# AC6901Demo0.net
KiCad netlist of a schematic drawn in Altium Designer
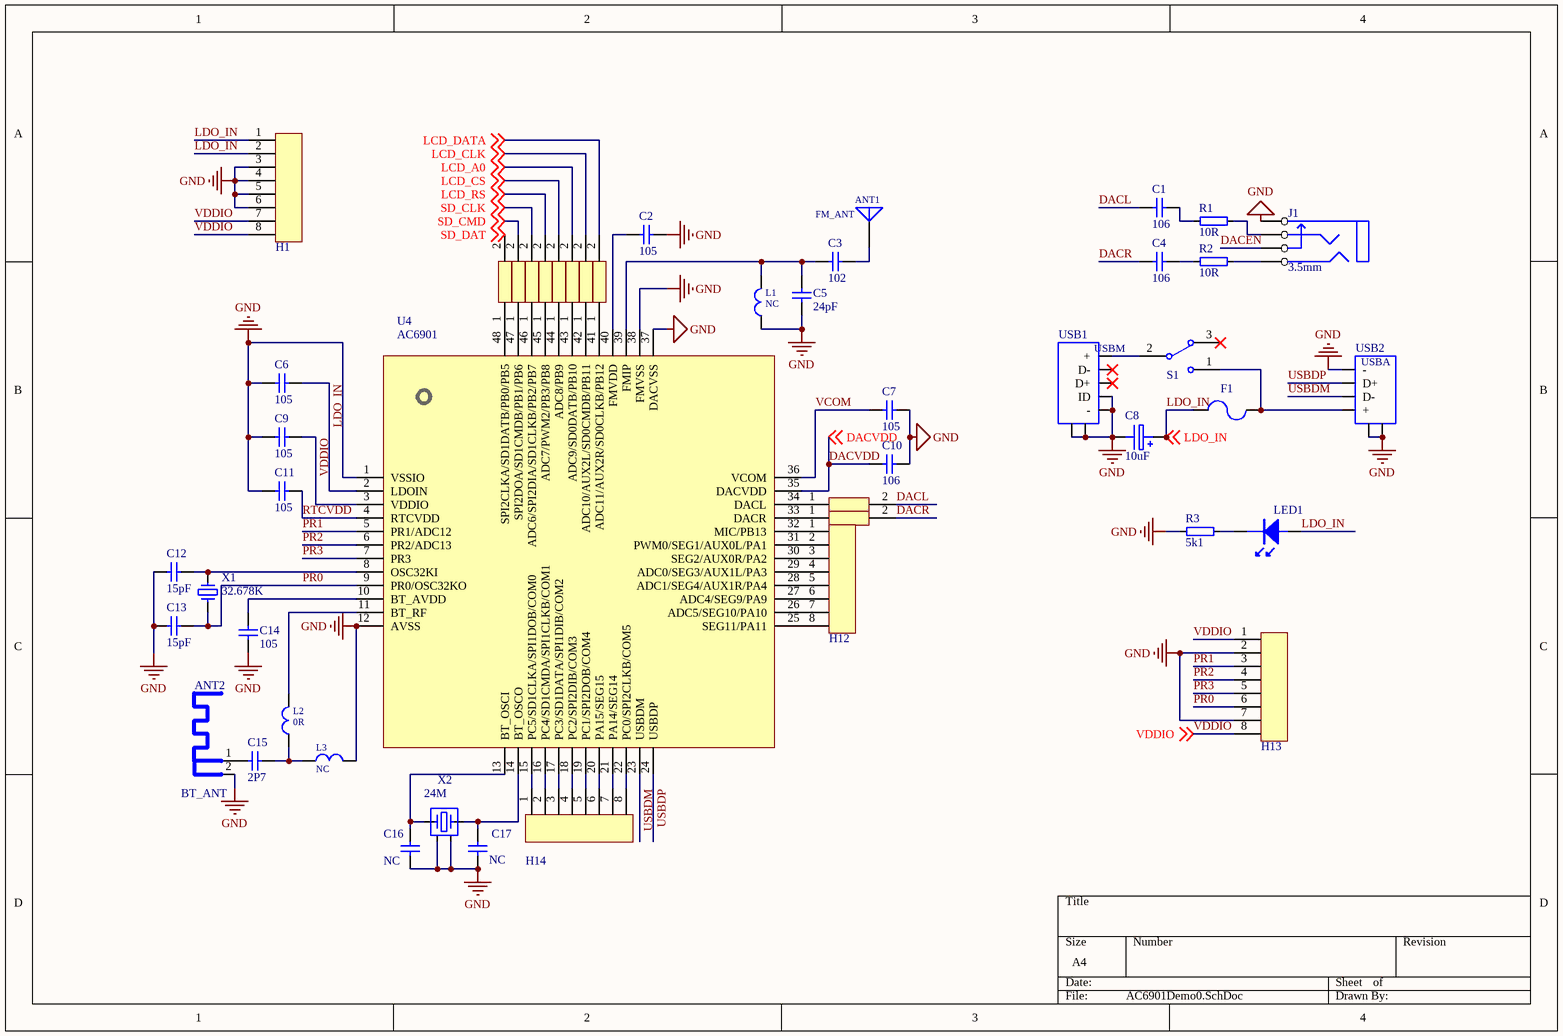
[diagram p0: AC6901Demo0.SchDoc]

(export (version "E")
  (design (tool "Eeschema 10.0.6"))
  (components
    (comp (ref "ANT1") (value "FM_ANT") (footprint "Demo:FM_ANT") (libsource (lib "Demo") (part "FM_ANT")))
    (comp (ref "ANT2")
      (value "BT_ANT")
      (footprint "Demo:ANT-F-2-2.4G")
      (libsource (lib "Demo") (part "BT_ANT"))
    )
    (comp (ref "C1") (value "106") (footprint "Demo:C 0805") (libsource (lib "Demo") (part "CAP-MLCC")))
    (comp (ref "C2") (value "105") (footprint "Demo:C 0805") (libsource (lib "Demo") (part "CAP-MLCC")))
    (comp (ref "C3") (value "102") (footprint "Demo:C 0805") (libsource (lib "Demo") (part "CAP-MLCC")))
    (comp (ref "C4") (value "106") (footprint "Demo:C 0805") (libsource (lib "Demo") (part "CAP-MLCC")))
    (comp (ref "C5") (value "24pF") (footprint "Demo:C 0805") (libsource (lib "Demo") (part "CAP-MLCC")))
    (comp (ref "C6") (value "105") (footprint "Demo:C 0805") (libsource (lib "Demo") (part "CAP-MLCC")))
    (comp (ref "C7") (value "105") (footprint "Demo:C 0805") (libsource (lib "Demo") (part "CAP-MLCC")))
    (comp (ref "C8") (value "10uF") (footprint "Demo:CTan(6032)") (libsource (lib "Demo") (part "CAP-ALE")))
    (comp (ref "C9") (value "105") (footprint "Demo:C 0805") (libsource (lib "Demo") (part "CAP-MLCC")))
    (comp (ref "C10") (value "106") (footprint "Demo:C 0805") (libsource (lib "Demo") (part "CAP-MLCC")))
    (comp (ref "C11") (value "105") (footprint "Demo:C 0805") (libsource (lib "Demo") (part "CAP-MLCC")))
    (comp (ref "C12") (value "15pF") (footprint "Demo:C 0805") (libsource (lib "Demo") (part "CAP-MLCC")))
    (comp (ref "C13") (value "15pF") (footprint "Demo:C 0805") (libsource (lib "Demo") (part "CAP-MLCC")))
    (comp (ref "C14") (value "105") (footprint "Demo:C 0805") (libsource (lib "Demo") (part "CAP-MLCC")))
    (comp (ref "C15") (value "2P7") (footprint "Demo:C 0805") (libsource (lib "Demo") (part "CAP-MLCC")))
    (comp (ref "C16") (value "NC") (footprint "Demo:C 0805") (libsource (lib "Demo") (part "CAP-MLCC")))
    (comp (ref "C17") (value "NC") (footprint "Demo:C 0805") (libsource (lib "Demo") (part "CAP-MLCC")))
    (comp (ref "F1") (value "FUSE") (footprint "Demo:F1808") (libsource (lib "Demo") (part "FUSE")))
    (comp (ref "H1") (value "HDR1X8") (footprint "Demo:HDR1X8") (libsource (lib "Demo") (part "HDR1X8")))
    (comp (ref "H2") (value "HDR2X1") (footprint "Demo:HDR2X1") (libsource (lib "") (part "HDR2X1_1")))
    (comp (ref "H3") (value "HDR2X1") (footprint "Demo:HDR2X1") (libsource (lib "") (part "HDR2X1_1")))
    (comp (ref "H4") (value "HDR2X1") (footprint "Demo:HDR2X1") (libsource (lib "") (part "HDR2X1_1")))
    (comp (ref "H5") (value "HDR2X1") (footprint "Demo:HDR2X1") (libsource (lib "") (part "HDR2X1_1")))
    (comp (ref "H6") (value "HDR2X1") (footprint "Demo:HDR2X1") (libsource (lib "") (part "HDR2X1_1")))
    (comp (ref "H7") (value "HDR2X1") (footprint "Demo:HDR2X1") (libsource (lib "") (part "HDR2X1_1")))
    (comp (ref "H8") (value "HDR2X1") (footprint "Demo:HDR2X1") (libsource (lib "") (part "HDR2X1_1")))
    (comp (ref "H9") (value "HDR2X1") (footprint "Demo:HDR2X1") (libsource (lib "") (part "HDR2X1_1")))
    (comp (ref "H10") (value "HDR2X1") (footprint "Demo:HDR2X1") (libsource (lib "Demo") (part "HDR2X1")))
    (comp (ref "H11") (value "HDR2X1") (footprint "Demo:HDR2X1") (libsource (lib "Demo") (part "HDR2X1")))
    (comp (ref "H12") (value "HDR1X8") (footprint "Demo:HDR1X8") (libsource (lib "Demo") (part "HDR1X8")))
    (comp (ref "H13") (value "HDR1X8") (footprint "Demo:HDR1X8") (libsource (lib "Demo") (part "HDR1X8")))
    (comp (ref "H14") (value "HDR1X8") (footprint "Demo:HDR1X8") (libsource (lib "") (part "HDR1X8_1")))
    (comp (ref "J1") (value "3.5mm") (footprint "Demo:AUX-3.5") (libsource (lib "Demo") (part "立体声插头")))
    (comp (ref "L1") (value "NC") (footprint "Demo:L 0805") (libsource (lib "Demo") (part "INDUCTOR")))
    (comp (ref "L2") (value "0R") (footprint "Demo:L 0805") (libsource (lib "Demo") (part "INDUCTOR")))
    (comp (ref "L3") (value "NC") (footprint "Demo:L 0805") (libsource (lib "Demo") (part "INDUCTOR")))
    (comp (ref "LED1") (value "LED") (footprint "Demo:LED 0805B") (libsource (lib "Demo") (part "LED")))
    (comp (ref "R1") (value "10R") (footprint "Demo:R 0805") (libsource (lib "Demo") (part "RES")))
    (comp (ref "R2") (value "10R") (footprint "Demo:R 0805") (libsource (lib "Demo") (part "RES")))
    (comp (ref "R3") (value "5k1") (footprint "Demo:R 0805") (libsource (lib "Demo") (part "RES")))
    (comp (ref "S1")
      (value "SW-SPDT")
      (footprint "Demo:MSK-12C01-07")
      (fields (field (name "PUBLISHER") "Altium Limited"))
      (libsource (lib "Demo") (part "SW-SPDT"))
    )
    (comp (ref "U4") (value "AC6901") (footprint "Demo:LQPF48") (libsource (lib "Demo") (part "AC6901")))
    (comp (ref "USB1")
      (value "USBmirco")
      (footprint "Demo:USB_micro")
      (libsource (lib "Demo") (part "USBmirco"))
    )
    (comp (ref "USB2") (value "USBA") (footprint "Demo:USB-A") (libsource (lib "Demo") (part "USBA")))
    (comp (ref "X1") (value "32.678K") (footprint "Demo:XTAL_3X8") (libsource (lib "Demo") (part "XTAL_3X8")))
    (comp (ref "X2")
      (value "24M")
      (footprint "Demo:XTAL_3225-4P")
      (libsource (lib "Demo") (part "XTAL_3325-4"))
    )
  )
  (nets
    (net (code "1") (name "/DACEN") (class "Default")
      (node (ref "J1") (pin "4") (pinfunction "4_4") (pintype "passive"))
    )
    (net (code "2") (name "/DACL") (class "Default")
      (node (ref "C1") (pin "1") (pinfunction "1_1") (pintype "passive"))
      (node (ref "H10") (pin "2") (pinfunction "2_2") (pintype "passive"))
    )
    (net (code "3") (name "/DACR") (class "Default")
      (node (ref "C4") (pin "1") (pinfunction "1_1") (pintype "passive"))
      (node (ref "H11") (pin "2") (pinfunction "2_2") (pintype "passive"))
    )
    (net (code "4") (name "/PR0") (class "Default")
      (node (ref "C13") (pin "2") (pinfunction "2_2") (pintype "passive"))
      (node (ref "H13") (pin "6") (pinfunction "6_6") (pintype "passive"))
      (node (ref "U4") (pin "9") (pinfunction "PR0/OSC32KO_9") (pintype "passive"))
      (node (ref "X1") (pin "2") (pinfunction "2_2") (pintype "passive"))
    )
    (net (code "5") (name "/PR1") (class "Default")
      (node (ref "H13") (pin "3") (pinfunction "3_3") (pintype "passive"))
      (node (ref "U4") (pin "5") (pinfunction "PR1/ADC12_5") (pintype "passive"))
    )
    (net (code "6") (name "/PR2") (class "Default")
      (node (ref "H13") (pin "4") (pinfunction "4_4") (pintype "passive"))
      (node (ref "U4") (pin "6") (pinfunction "PR2/ADC13_6") (pintype "passive"))
    )
    (net (code "7") (name "/PR3") (class "Default")
      (node (ref "H13") (pin "5") (pinfunction "5_5") (pintype "passive"))
      (node (ref "U4") (pin "7") (pinfunction "PR3_7") (pintype "passive"))
    )
    (net (code "8") (name "/RTCVDD") (class "Default")
      (node (ref "C11") (pin "1") (pinfunction "1_1") (pintype "passive"))
      (node (ref "U4") (pin "4") (pinfunction "RTCVDD_4") (pintype "passive"))
    )
    (net (code "9") (name "/USBDM") (class "Default")
      (node (ref "U4") (pin "23") (pinfunction "USBDM_23") (pintype "passive"))
      (node (ref "USB2") (pin "2") (pinfunction "D-_2") (pintype "passive"))
    )
    (net (code "10") (name "/USBDP") (class "Default")
      (node (ref "U4") (pin "24") (pinfunction "USBDP_24") (pintype "passive"))
      (node (ref "USB2") (pin "3") (pinfunction "D+_3") (pintype "passive"))
    )
    (net (code "11") (name "/VCOM") (class "Default")
      (node (ref "C7") (pin "1") (pinfunction "1_1") (pintype "passive"))
      (node (ref "U4") (pin "36") (pinfunction "VCOM_36") (pintype "passive"))
    )
    (net (code "12") (name "DACVDD") (class "Default")
      (node (ref "C10") (pin "1") (pinfunction "1_1") (pintype "passive"))
      (node (ref "U4") (pin "35") (pinfunction "DACVDD_35") (pintype "passive"))
    )
    (net (code "13") (name "GND") (class "Default")
      (node (ref "ANT2") (pin "2") (pinfunction "2_2") (pintype "passive"))
      (node (ref "C10") (pin "2") (pinfunction "2_2") (pintype "passive"))
      (node (ref "C11") (pin "2") (pinfunction "2_2") (pintype "passive"))
      (node (ref "C12") (pin "1") (pinfunction "1_1") (pintype "passive"))
      (node (ref "C13") (pin "1") (pinfunction "1_1") (pintype "passive"))
      (node (ref "C14") (pin "1") (pinfunction "1_1") (pintype "passive"))
      (node (ref "C16") (pin "2") (pinfunction "2_2") (pintype "passive"))
      (node (ref "C17") (pin "1") (pinfunction "1_1") (pintype "passive"))
      (node (ref "C2") (pin "1") (pinfunction "1_1") (pintype "passive"))
      (node (ref "C5") (pin "2") (pinfunction "2_2") (pintype "passive"))
      (node (ref "C6") (pin "2") (pinfunction "2_2") (pintype "passive"))
      (node (ref "C7") (pin "2") (pinfunction "2_2") (pintype "passive"))
      (node (ref "C8") (pin "2") (pinfunction "2_2") (pintype "passive"))
      (node (ref "C9") (pin "2") (pinfunction "2_2") (pintype "passive"))
      (node (ref "H1") (pin "3") (pinfunction "3_3") (pintype "passive"))
      (node (ref "H1") (pin "4") (pinfunction "4_4") (pintype "passive"))
      (node (ref "H1") (pin "5") (pinfunction "5_5") (pintype "passive"))
      (node (ref "H1") (pin "6") (pinfunction "6_6") (pintype "passive"))
      (node (ref "H13") (pin "2") (pinfunction "2_2") (pintype "passive"))
      (node (ref "H13") (pin "7") (pinfunction "7_7") (pintype "passive"))
      (node (ref "J1") (pin "1") (pinfunction "1_1") (pintype "passive"))
      (node (ref "L1") (pin "1") (pinfunction "1_1") (pintype "passive"))
      (node (ref "L3") (pin "2") (pinfunction "2_2") (pintype "passive"))
      (node (ref "R3") (pin "1") (pinfunction "1_1") (pintype "passive"))
      (node (ref "U4") (pin "1") (pinfunction "VSSIO_1") (pintype "power_in"))
      (node (ref "U4") (pin "12") (pinfunction "AVSS_12") (pintype "passive"))
      (node (ref "U4") (pin "37") (pinfunction "DACVSS_37") (pintype "passive"))
      (node (ref "U4") (pin "38") (pinfunction "FMVSS_38") (pintype "passive"))
      (node (ref "USB1") (pin "4") (pinfunction "ID_4") (pintype "passive"))
      (node (ref "USB1") (pin "5") (pinfunction "-_5") (pintype "passive"))
      (node (ref "USB1") (pin "GND") (pinfunction "GND_GND") (pintype "passive"))
      (node (ref "USB2") (pin "4") (pinfunction "-_4") (pintype "passive"))
      (node (ref "USB2") (pin "5") (pinfunction "GND_5") (pintype "passive"))
      (node (ref "X2") (pin "2") (pinfunction "2_2") (pintype "passive"))
      (node (ref "X2") (pin "4") (pinfunction "4_4") (pintype "passive"))
    )
    (net (code "14") (name "LCD_A0") (class "Default")
      (node (ref "H7") (pin "2") (pinfunction "2_2") (pintype "passive"))
    )
    (net (code "15") (name "LCD_CLK") (class "Default")
      (node (ref "H8") (pin "2") (pinfunction "2_2") (pintype "passive"))
    )
    (net (code "16") (name "LCD_CS") (class "Default")
      (node (ref "H6") (pin "2") (pinfunction "2_2") (pintype "passive"))
    )
    (net (code "17") (name "LCD_DATA") (class "Default")
      (node (ref "H9") (pin "2") (pinfunction "2_2") (pintype "passive"))
    )
    (net (code "18") (name "LCD_RS") (class "Default")
      (node (ref "H5") (pin "2") (pinfunction "2_2") (pintype "passive"))
    )
    (net (code "19") (name "LDO_IN") (class "Default")
      (node (ref "C6") (pin "1") (pinfunction "1_1") (pintype "passive"))
      (node (ref "C8") (pin "1") (pinfunction "1_1") (pintype "passive"))
      (node (ref "F1") (pin "1") (pinfunction "1_1") (pintype "passive"))
      (node (ref "H1") (pin "1") (pinfunction "1_1") (pintype "passive"))
      (node (ref "H1") (pin "2") (pinfunction "2_2") (pintype "passive"))
      (node (ref "LED1") (pin "1") (pinfunction "1_1") (pintype "passive"))
      (node (ref "U4") (pin "2") (pinfunction "LDOIN_2") (pintype "power_in"))
    )
    (net (code "20") (name "Net-(ANT1-Pad1)") (class "Default")
      (node (ref "ANT1") (pin "1") (pinfunction "1_1") (pintype "passive"))
      (node (ref "C3") (pin "2") (pinfunction "2_2") (pintype "passive"))
    )
    (net (code "21") (name "Net-(ANT2-Pad1)") (class "Default")
      (node (ref "ANT2") (pin "1") (pinfunction "1_1") (pintype "passive"))
      (node (ref "C15") (pin "1") (pinfunction "1_1") (pintype "passive"))
    )
    (net (code "22") (name "Net-(C1-Pad2)") (class "Default")
      (node (ref "C1") (pin "2") (pinfunction "2_2") (pintype "passive"))
      (node (ref "R1") (pin "1") (pinfunction "1_1") (pintype "passive"))
    )
    (net (code "23") (name "Net-(C4-Pad2)") (class "Default")
      (node (ref "C4") (pin "2") (pinfunction "2_2") (pintype "passive"))
      (node (ref "R2") (pin "1") (pinfunction "1_1") (pintype "passive"))
    )
    (net (code "24") (name "Net-(C15-Pad2)") (class "Default")
      (node (ref "C15") (pin "2") (pinfunction "2_2") (pintype "passive"))
      (node (ref "L2") (pin "1") (pinfunction "1_1") (pintype "passive"))
      (node (ref "L3") (pin "1") (pinfunction "1_1") (pintype "passive"))
    )
    (net (code "25") (name "Net-(J1-Pad2)") (class "Default")
      (node (ref "J1") (pin "2") (pinfunction "2_2") (pintype "passive"))
      (node (ref "R1") (pin "2") (pinfunction "2_2") (pintype "passive"))
    )
    (net (code "26") (name "Net-(J1-Pad3)") (class "Default")
      (node (ref "J1") (pin "3") (pinfunction "3_3") (pintype "passive"))
      (node (ref "R2") (pin "2") (pinfunction "2_2") (pintype "passive"))
    )
    (net (code "27") (name "Net-(LED1-Pad2)") (class "Default")
      (node (ref "LED1") (pin "2") (pinfunction "2_2") (pintype "passive"))
      (node (ref "R3") (pin "2") (pinfunction "2_2") (pintype "passive"))
    )
    (net (code "28") (name "Net-(U4-ADC0{slash}SEG3{slash}AUX1L{slash}PA3)") (class "Default")
      (node (ref "H12") (pin "4") (pinfunction "4_4") (pintype "passive"))
      (node (ref "U4") (pin "29") (pinfunction "ADC0/SEG3/AUX1L/PA3_29") (pintype "passive"))
    )
    (net (code "29") (name "Net-(U4-ADC1{slash}SEG4{slash}AUX1R{slash}PA4)") (class "Default")
      (node (ref "H12") (pin "5") (pinfunction "5_5") (pintype "passive"))
      (node (ref "U4") (pin "28") (pinfunction "ADC1/SEG4/AUX1R/PA4_28") (pintype "passive"))
    )
    (net (code "30") (name "Net-(U4-ADC4{slash}SEG9{slash}PA9)") (class "Default")
      (node (ref "H12") (pin "6") (pinfunction "6_6") (pintype "passive"))
      (node (ref "U4") (pin "27") (pinfunction "ADC4/SEG9/PA9_27") (pintype "passive"))
    )
    (net (code "31") (name "Net-(U4-ADC5{slash}SEG10{slash}PA10)") (class "Default")
      (node (ref "H12") (pin "7") (pinfunction "7_7") (pintype "passive"))
      (node (ref "U4") (pin "26") (pinfunction "ADC5/SEG10/PA10_26") (pintype "passive"))
    )
    (net (code "32") (name "Net-(U4-ADC6{slash}SPI2DIA{slash}SD1CLKB{slash}PB2{slash}PB7)") (class "Default")
      (node (ref "H4") (pin "1") (pinfunction "1_1") (pintype "passive"))
      (node (ref "U4") (pin "46") (pinfunction "ADC6/SPI2DIA/SD1CLKB/PB2/PB7_46") (pintype "passive"))
    )
    (net (code "33") (name "Net-(U4-ADC7{slash}PWM2{slash}PB3{slash}PB8)") (class "Default")
      (node (ref "H5") (pin "1") (pinfunction "1_1") (pintype "passive"))
      (node (ref "U4") (pin "45") (pinfunction "ADC7/PWM2/PB3/PB8_45") (pintype "passive"))
    )
    (net (code "34") (name "Net-(U4-ADC8{slash}PB9)") (class "Default")
      (node (ref "H6") (pin "1") (pinfunction "1_1") (pintype "passive"))
      (node (ref "U4") (pin "44") (pinfunction "ADC8/PB9_44") (pintype "passive"))
    )
    (net (code "35") (name "Net-(U4-ADC9{slash}SD0DATB{slash}PB10)") (class "Default")
      (node (ref "H7") (pin "1") (pinfunction "1_1") (pintype "passive"))
      (node (ref "U4") (pin "43") (pinfunction "ADC9/SD0DATB/PB10_43") (pintype "passive"))
    )
    (net (code "36") (name "Net-(U4-ADC10{slash}AUX2L{slash}SD0CMDB{slash}PB11)") (class "Default")
      (node (ref "H8") (pin "1") (pinfunction "1_1") (pintype "passive"))
      (node (ref "U4") (pin "42") (pinfunction "ADC10/AUX2L/SD0CMDB/PB11_42") (pintype "passive"))
    )
    (net (code "37") (name "Net-(U4-ADC11{slash}AUX2R{slash}SD0CLKB{slash}PB12)") (class "Default")
      (node (ref "H9") (pin "1") (pinfunction "1_1") (pintype "passive"))
      (node (ref "U4") (pin "41") (pinfunction "ADC11/AUX2R/SD0CLKB/PB12_41") (pintype "passive"))
    )
    (net (code "38") (name "Net-(U4-BT_AVDD)") (class "Default")
      (node (ref "C14") (pin "2") (pinfunction "2_2") (pintype "passive"))
      (node (ref "U4") (pin "10") (pinfunction "BT_AVDD_10") (pintype "passive"))
    )
    (net (code "39") (name "Net-(U4-BT_OSCI)") (class "Default")
      (node (ref "C16") (pin "1") (pinfunction "1_1") (pintype "passive"))
      (node (ref "U4") (pin "13") (pinfunction "BT_OSCI_13") (pintype "passive"))
      (node (ref "X2") (pin "3") (pinfunction "3_3") (pintype "passive"))
    )
    (net (code "40") (name "Net-(U4-BT_OSCO)") (class "Default")
      (node (ref "C17") (pin "2") (pinfunction "2_2") (pintype "passive"))
      (node (ref "U4") (pin "14") (pinfunction "BT_OSCO_14") (pintype "passive"))
      (node (ref "X2") (pin "1") (pinfunction "1_1") (pintype "passive"))
    )
    (net (code "41") (name "Net-(U4-BT_RF)") (class "Default")
      (node (ref "L2") (pin "2") (pinfunction "2_2") (pintype "passive"))
      (node (ref "U4") (pin "11") (pinfunction "BT_RF_11") (pintype "passive"))
    )
    (net (code "42") (name "Net-(U4-DACL)") (class "Default")
      (node (ref "H10") (pin "1") (pinfunction "1_1") (pintype "passive"))
      (node (ref "U4") (pin "34") (pinfunction "DACL_34") (pintype "passive"))
    )
    (net (code "43") (name "Net-(U4-DACR)") (class "Default")
      (node (ref "H11") (pin "1") (pinfunction "1_1") (pintype "passive"))
      (node (ref "U4") (pin "33") (pinfunction "DACR_33") (pintype "passive"))
    )
    (net (code "44") (name "Net-(U4-FMIP)") (class "Default")
      (node (ref "C3") (pin "1") (pinfunction "1_1") (pintype "passive"))
      (node (ref "C5") (pin "1") (pinfunction "1_1") (pintype "passive"))
      (node (ref "L1") (pin "2") (pinfunction "2_2") (pintype "passive"))
      (node (ref "U4") (pin "39") (pinfunction "FMIP_39") (pintype "passive"))
    )
    (net (code "45") (name "Net-(U4-FMVDD)") (class "Default")
      (node (ref "C2") (pin "2") (pinfunction "2_2") (pintype "passive"))
      (node (ref "U4") (pin "40") (pinfunction "FMVDD_40") (pintype "passive"))
    )
    (net (code "46") (name "Net-(U4-MIC{slash}PB13)") (class "Default")
      (node (ref "H12") (pin "1") (pinfunction "1_1") (pintype "passive"))
      (node (ref "U4") (pin "32") (pinfunction "MIC/PB13_32") (pintype "passive"))
    )
    (net (code "47") (name "Net-(U4-OSC32KI)") (class "Default")
      (node (ref "C12") (pin "2") (pinfunction "2_2") (pintype "passive"))
      (node (ref "U4") (pin "8") (pinfunction "OSC32KI_8") (pintype "passive"))
      (node (ref "X1") (pin "1") (pinfunction "1_1") (pintype "passive"))
    )
    (net (code "48") (name "Net-(U4-PA14{slash}SEG14)") (class "Default")
      (node (ref "H14") (pin "7") (pinfunction "7_7") (pintype "passive"))
      (node (ref "U4") (pin "21") (pinfunction "PA14/SEG14_21") (pintype "passive"))
    )
    (net (code "49") (name "Net-(U4-PA15{slash}SEG15)") (class "Default")
      (node (ref "H14") (pin "6") (pinfunction "6_6") (pintype "passive"))
      (node (ref "U4") (pin "20") (pinfunction "PA15/SEG15_20") (pintype "passive"))
    )
    (net (code "50") (name "Net-(U4-PC0{slash}SPI2CLKB{slash}COM5)") (class "Default")
      (node (ref "H14") (pin "8") (pinfunction "8_8") (pintype "passive"))
      (node (ref "U4") (pin "22") (pinfunction "PC0/SPI2CLKB/COM5_22") (pintype "passive"))
    )
    (net (code "51") (name "Net-(U4-PC1{slash}SPI2DOB{slash}COM4)") (class "Default")
      (node (ref "H14") (pin "5") (pinfunction "5_5") (pintype "passive"))
      (node (ref "U4") (pin "19") (pinfunction "PC1/SPI2DOB/COM4_19") (pintype "passive"))
    )
    (net (code "52") (name "Net-(U4-PC2{slash}SPI2DIB{slash}COM3)") (class "Default")
      (node (ref "H14") (pin "4") (pinfunction "4_4") (pintype "passive"))
      (node (ref "U4") (pin "18") (pinfunction "PC2/SPI2DIB/COM3_18") (pintype "passive"))
    )
    (net (code "53") (name "Net-(U4-PC3{slash}SD1DATA{slash}SPI1DIB{slash}COM2)") (class "Default")
      (node (ref "H14") (pin "3") (pinfunction "3_3") (pintype "passive"))
      (node (ref "U4") (pin "17") (pinfunction "PC3/SD1DATA/SPI1DIB/COM2_17") (pintype "passive"))
    )
    (net (code "54") (name "Net-(U4-PC4{slash}SD1CMDA{slash}SPI1CLKB{slash}COM1)") (class "Default")
      (node (ref "H14") (pin "2") (pinfunction "2_2") (pintype "passive"))
      (node (ref "U4") (pin "16") (pinfunction "PC4/SD1CMDA/SPI1CLKB/COM1_16") (pintype "passive"))
    )
    (net (code "55") (name "Net-(U4-PC5{slash}SD1CLKA{slash}SPI1DOB{slash}COM0)") (class "Default")
      (node (ref "H14") (pin "1") (pinfunction "1_1") (pintype "passive"))
      (node (ref "U4") (pin "15") (pinfunction "PC5/SD1CLKA/SPI1DOB/COM0_15") (pintype "passive"))
    )
    (net (code "56") (name "Net-(U4-PWM0{slash}SEG1{slash}AUX0L{slash}PA1)") (class "Default")
      (node (ref "H12") (pin "2") (pinfunction "2_2") (pintype "passive"))
      (node (ref "U4") (pin "31") (pinfunction "PWM0/SEG1/AUX0L/PA1_31") (pintype "passive"))
    )
    (net (code "57") (name "Net-(U4-SEG2{slash}AUX0R{slash}PA2)") (class "Default")
      (node (ref "H12") (pin "3") (pinfunction "3_3") (pintype "passive"))
      (node (ref "U4") (pin "30") (pinfunction "SEG2/AUX0R/PA2_30") (pintype "passive"))
    )
    (net (code "58") (name "Net-(U4-SEG11{slash}PA11)") (class "Default")
      (node (ref "H12") (pin "8") (pinfunction "8_8") (pintype "passive"))
      (node (ref "U4") (pin "25") (pinfunction "SEG11/PA11_25") (pintype "passive"))
    )
    (net (code "59") (name "Net-(U4-SPI2CLKA{slash}SD1DATB{slash}PB0{slash}PB5)") (class "Default")
      (node (ref "H2") (pin "1") (pinfunction "1_1") (pintype "passive"))
      (node (ref "U4") (pin "48") (pinfunction "SPI2CLKA/SD1DATB/PB0/PB5_48") (pintype "passive"))
    )
    (net (code "60") (name "Net-(U4-SPI2DOA{slash}SD1CMDB{slash}PB1{slash}PB6)") (class "Default")
      (node (ref "H3") (pin "1") (pinfunction "1_1") (pintype "passive"))
      (node (ref "U4") (pin "47") (pinfunction "SPI2DOA/SD1CMDB/PB1/PB6_47") (pintype "passive"))
    )
    (net (code "61") (name "Net-(USB1-+)") (class "Default")
      (node (ref "S1") (pin "2") (pinfunction "2_2") (pintype "passive"))
      (node (ref "USB1") (pin "1") (pinfunction "+_1") (pintype "passive"))
    )
    (net (code "62") (name "Net-(USB2-+)") (class "Default")
      (node (ref "F1") (pin "2") (pinfunction "2_2") (pintype "passive"))
      (node (ref "S1") (pin "1") (pinfunction "1_1") (pintype "passive"))
      (node (ref "USB2") (pin "1") (pinfunction "+_1") (pintype "passive"))
    )
    (net (code "63") (name "SD_CLK") (class "Default")
      (node (ref "H4") (pin "2") (pinfunction "2_2") (pintype "passive"))
    )
    (net (code "64") (name "SD_CMD") (class "Default")
      (node (ref "H3") (pin "2") (pinfunction "2_2") (pintype "passive"))
    )
    (net (code "65") (name "SD_DAT") (class "Default")
      (node (ref "H2") (pin "2") (pinfunction "2_2") (pintype "passive"))
    )
    (net (code "66") (name "VDDIO") (class "Default")
      (node (ref "C9") (pin "1") (pinfunction "1_1") (pintype "passive"))
      (node (ref "H1") (pin "7") (pinfunction "7_7") (pintype "passive"))
      (node (ref "H1") (pin "8") (pinfunction "8_8") (pintype "passive"))
      (node (ref "H13") (pin "1") (pinfunction "1_1") (pintype "passive"))
      (node (ref "H13") (pin "8") (pinfunction "8_8") (pintype "passive"))
      (node (ref "U4") (pin "3") (pinfunction "VDDIO_3") (pintype "passive"))
    )
    (net (code "67") (name "unconnected-(S1-Pad3)") (class "Default")
      (node (ref "S1") (pin "3") (pinfunction "3_3") (pintype "passive+no_connect"))
    )
    (net (code "68") (name "unconnected-(USB1-D+-Pad3)") (class "Default")
      (node (ref "USB1") (pin "3") (pinfunction "D+_3") (pintype "passive+no_connect"))
    )
    (net (code "69") (name "unconnected-(USB1-D--Pad2)") (class "Default")
      (node (ref "USB1") (pin "2") (pinfunction "D-_2") (pintype "passive+no_connect"))
    )
  )
)
